# czad.net
KiCad netlist of a schematic drawn in Altium Designer
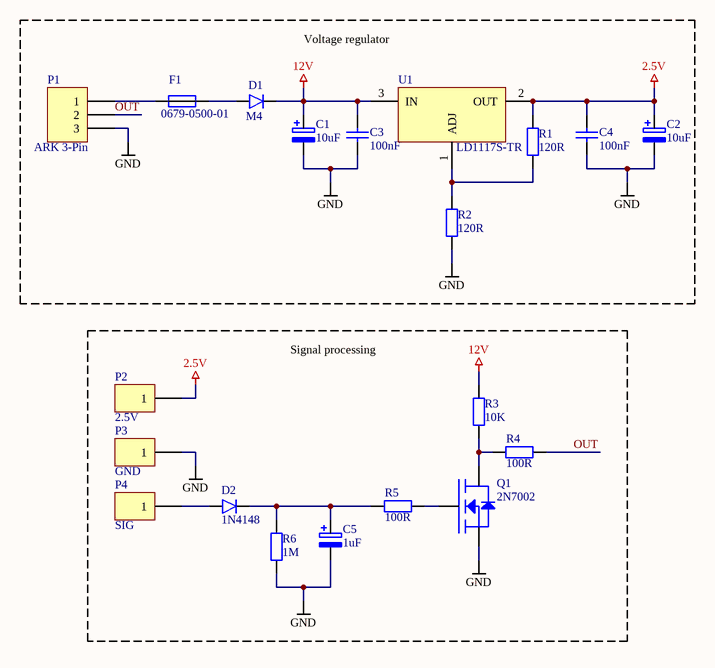
[diagram p0: czad.SchDoc]

(export (version "E")
  (design (tool "Eeschema 10.0.6"))
  (components
    (comp (ref "C1")
      (value "10uF")
      (footprint "TANC_B")
      (description "Capacitor Polarized")
      (libsource (lib "Library") (part "Cap_Pol"))
    )
    (comp (ref "C2")
      (value "10uF")
      (footprint "TANC_B")
      (description "Capacitor Polarized")
      (libsource (lib "Library") (part "Cap_Pol"))
    )
    (comp (ref "C3")
      (value "100nF")
      (footprint "C0805")
      (description "Capacitor")
      (libsource (lib "Library") (part "Cap"))
    )
    (comp (ref "C4")
      (value "100nF")
      (footprint "C0805")
      (description "Capacitor")
      (libsource (lib "Library") (part "Cap"))
    )
    (comp (ref "C5")
      (value "1uF")
      (footprint "TANC_A")
      (description "Capacitor Polarized")
      (libsource (lib "Library") (part "Cap_Pol"))
    )
    (comp (ref "D1") (value "M4") (footprint "SMA") (libsource (lib "Library") (part "Diode")))
    (comp (ref "D2") (value "1N4148") (footprint "DO-213A") (libsource (lib "Library") (part "Diode")))
    (comp (ref "F1")
      (value "0679-0500-01")
      (footprint "0679-0500-01")
      (description "Bezpiecznik: topikowy; szybki; ceramiczny; 500mA; 125VAC; 125VDC")
      (libsource (lib "Library") (part "0679-0500-01"))
    )
    (comp (ref "P1")
      (value "ARK 3-Pin")
      (footprint "ARK-3.5mm-3pin")
      (libsource (lib "Connectors") (part "ARK 3-Pin"))
    )
    (comp (ref "P2")
      (value "2.5V")
      (footprint "PAD")
      (description "PAD")
      (libsource (lib "Connectors") (part "PAD"))
    )
    (comp (ref "P3")
      (value "GND")
      (footprint "PAD")
      (description "PAD")
      (libsource (lib "Connectors") (part "PAD"))
    )
    (comp (ref "P4")
      (value "SIG")
      (footprint "PAD")
      (description "PAD")
      (libsource (lib "Connectors") (part "PAD"))
    )
    (comp (ref "Q1")
      (value "2N7002")
      (footprint "SOT23")
      (description "N-MOSFET")
      (libsource (lib "Library") (part "2N7002(GSD)"))
    )
    (comp (ref "R1")
      (value "120R")
      (footprint "R0805")
      (description "Resistor")
      (libsource (lib "Library") (part "Res"))
    )
    (comp (ref "R2")
      (value "120R")
      (footprint "R0805")
      (description "Resistor")
      (libsource (lib "Library") (part "Res"))
    )
    (comp (ref "R3")
      (value "10K")
      (footprint "R0805")
      (description "Resistor")
      (libsource (lib "Library") (part "Res"))
    )
    (comp (ref "R4")
      (value "100R")
      (footprint "R0805")
      (description "Resistor")
      (libsource (lib "") (part "Res_1"))
    )
    (comp (ref "R5")
      (value "100R")
      (footprint "R0805")
      (description "Resistor")
      (libsource (lib "") (part "Res_1"))
    )
    (comp (ref "R6")
      (value "1M")
      (footprint "R0805")
      (description "Resistor")
      (libsource (lib "") (part "Res_2"))
    )
    (comp (ref "U1")
      (value "LD1117S-TR")
      (footprint "SOT-223")
      (description "Stabilizator napiêcia; LDO, liniowy, regulowany; 1,25÷15V; 0,95A")
      (libsource (lib "IC") (part "LD1117S-TR"))
    )
  )
  (nets
    (net (code "1") (name "/OUT") (class "Default")
      (node (ref "P1") (pin "2") (pinfunction "2_2") (pintype "passive"))
      (node (ref "R4") (pin "1") (pinfunction "1_1") (pintype "passive"))
    )
    (net (code "2") (name "2.5V") (class "Default")
      (node (ref "C2") (pin "1") (pinfunction "1_1") (pintype "passive"))
      (node (ref "C4") (pin "1") (pinfunction "1_1") (pintype "passive"))
      (node (ref "P2") (pin "1") (pinfunction "1_1") (pintype "passive"))
      (node (ref "R1") (pin "1") (pinfunction "1_1") (pintype "passive"))
      (node (ref "U1") (pin "2") (pinfunction "OUT_2") (pintype "power_in"))
    )
    (net (code "3") (name "12V") (class "Default")
      (node (ref "C1") (pin "1") (pinfunction "1_1") (pintype "passive"))
      (node (ref "C3") (pin "1") (pinfunction "1_1") (pintype "passive"))
      (node (ref "D1") (pin "1") (pinfunction "1_1") (pintype "power_in"))
      (node (ref "R3") (pin "1") (pinfunction "1_1") (pintype "passive"))
      (node (ref "U1") (pin "3") (pinfunction "IN_3") (pintype "power_in"))
    )
    (net (code "4") (name "GND") (class "Default")
      (node (ref "C1") (pin "2") (pinfunction "2_2") (pintype "passive"))
      (node (ref "C2") (pin "2") (pinfunction "2_2") (pintype "passive"))
      (node (ref "C3") (pin "2") (pinfunction "2_2") (pintype "passive"))
      (node (ref "C4") (pin "2") (pinfunction "2_2") (pintype "passive"))
      (node (ref "C5") (pin "2") (pinfunction "2_2") (pintype "passive"))
      (node (ref "P1") (pin "3") (pinfunction "3_3") (pintype "passive"))
      (node (ref "P3") (pin "1") (pinfunction "1_1") (pintype "passive"))
      (node (ref "Q1") (pin "2") (pinfunction "S_2") (pintype "passive"))
      (node (ref "R2") (pin "2") (pinfunction "2_2") (pintype "passive"))
      (node (ref "R6") (pin "1") (pinfunction "1_1") (pintype "passive"))
    )
    (net (code "5") (name "Net-(C5-Pad1)") (class "Default")
      (node (ref "C5") (pin "1") (pinfunction "1_1") (pintype "passive"))
      (node (ref "D2") (pin "1") (pinfunction "1_1") (pintype "power_in"))
      (node (ref "R5") (pin "2") (pinfunction "2_2") (pintype "passive"))
      (node (ref "R6") (pin "2") (pinfunction "2_2") (pintype "passive"))
    )
    (net (code "6") (name "Net-(D1-Pad2)") (class "Default")
      (node (ref "D1") (pin "2") (pinfunction "2_2") (pintype "power_in"))
      (node (ref "F1") (pin "2") (pinfunction "2_2") (pintype "passive"))
    )
    (net (code "7") (name "Net-(D2-Pad2)") (class "Default")
      (node (ref "D2") (pin "2") (pinfunction "2_2") (pintype "power_in"))
      (node (ref "P4") (pin "1") (pinfunction "1_1") (pintype "passive"))
    )
    (net (code "8") (name "Net-(F1-Pad1)") (class "Default")
      (node (ref "F1") (pin "1") (pinfunction "1_1") (pintype "passive"))
      (node (ref "P1") (pin "1") (pinfunction "1_1") (pintype "passive"))
    )
    (net (code "9") (name "Net-(Q1-D)") (class "Default")
      (node (ref "Q1") (pin "3") (pinfunction "D_3") (pintype "passive"))
      (node (ref "R3") (pin "2") (pinfunction "2_2") (pintype "passive"))
      (node (ref "R4") (pin "2") (pinfunction "2_2") (pintype "passive"))
    )
    (net (code "10") (name "Net-(Q1-G)") (class "Default")
      (node (ref "Q1") (pin "1") (pinfunction "G_1") (pintype "passive"))
      (node (ref "R5") (pin "1") (pinfunction "1_1") (pintype "passive"))
    )
    (net (code "11") (name "Net-(U1-ADJ)") (class "Default")
      (node (ref "R1") (pin "2") (pinfunction "2_2") (pintype "passive"))
      (node (ref "R2") (pin "1") (pinfunction "1_1") (pintype "passive"))
      (node (ref "U1") (pin "1") (pinfunction "ADJ_1") (pintype "power_in"))
    )
  )
)
